# FreidoraAireCuki.net
KiCad netlist of a schematic drawn in Altium Designer
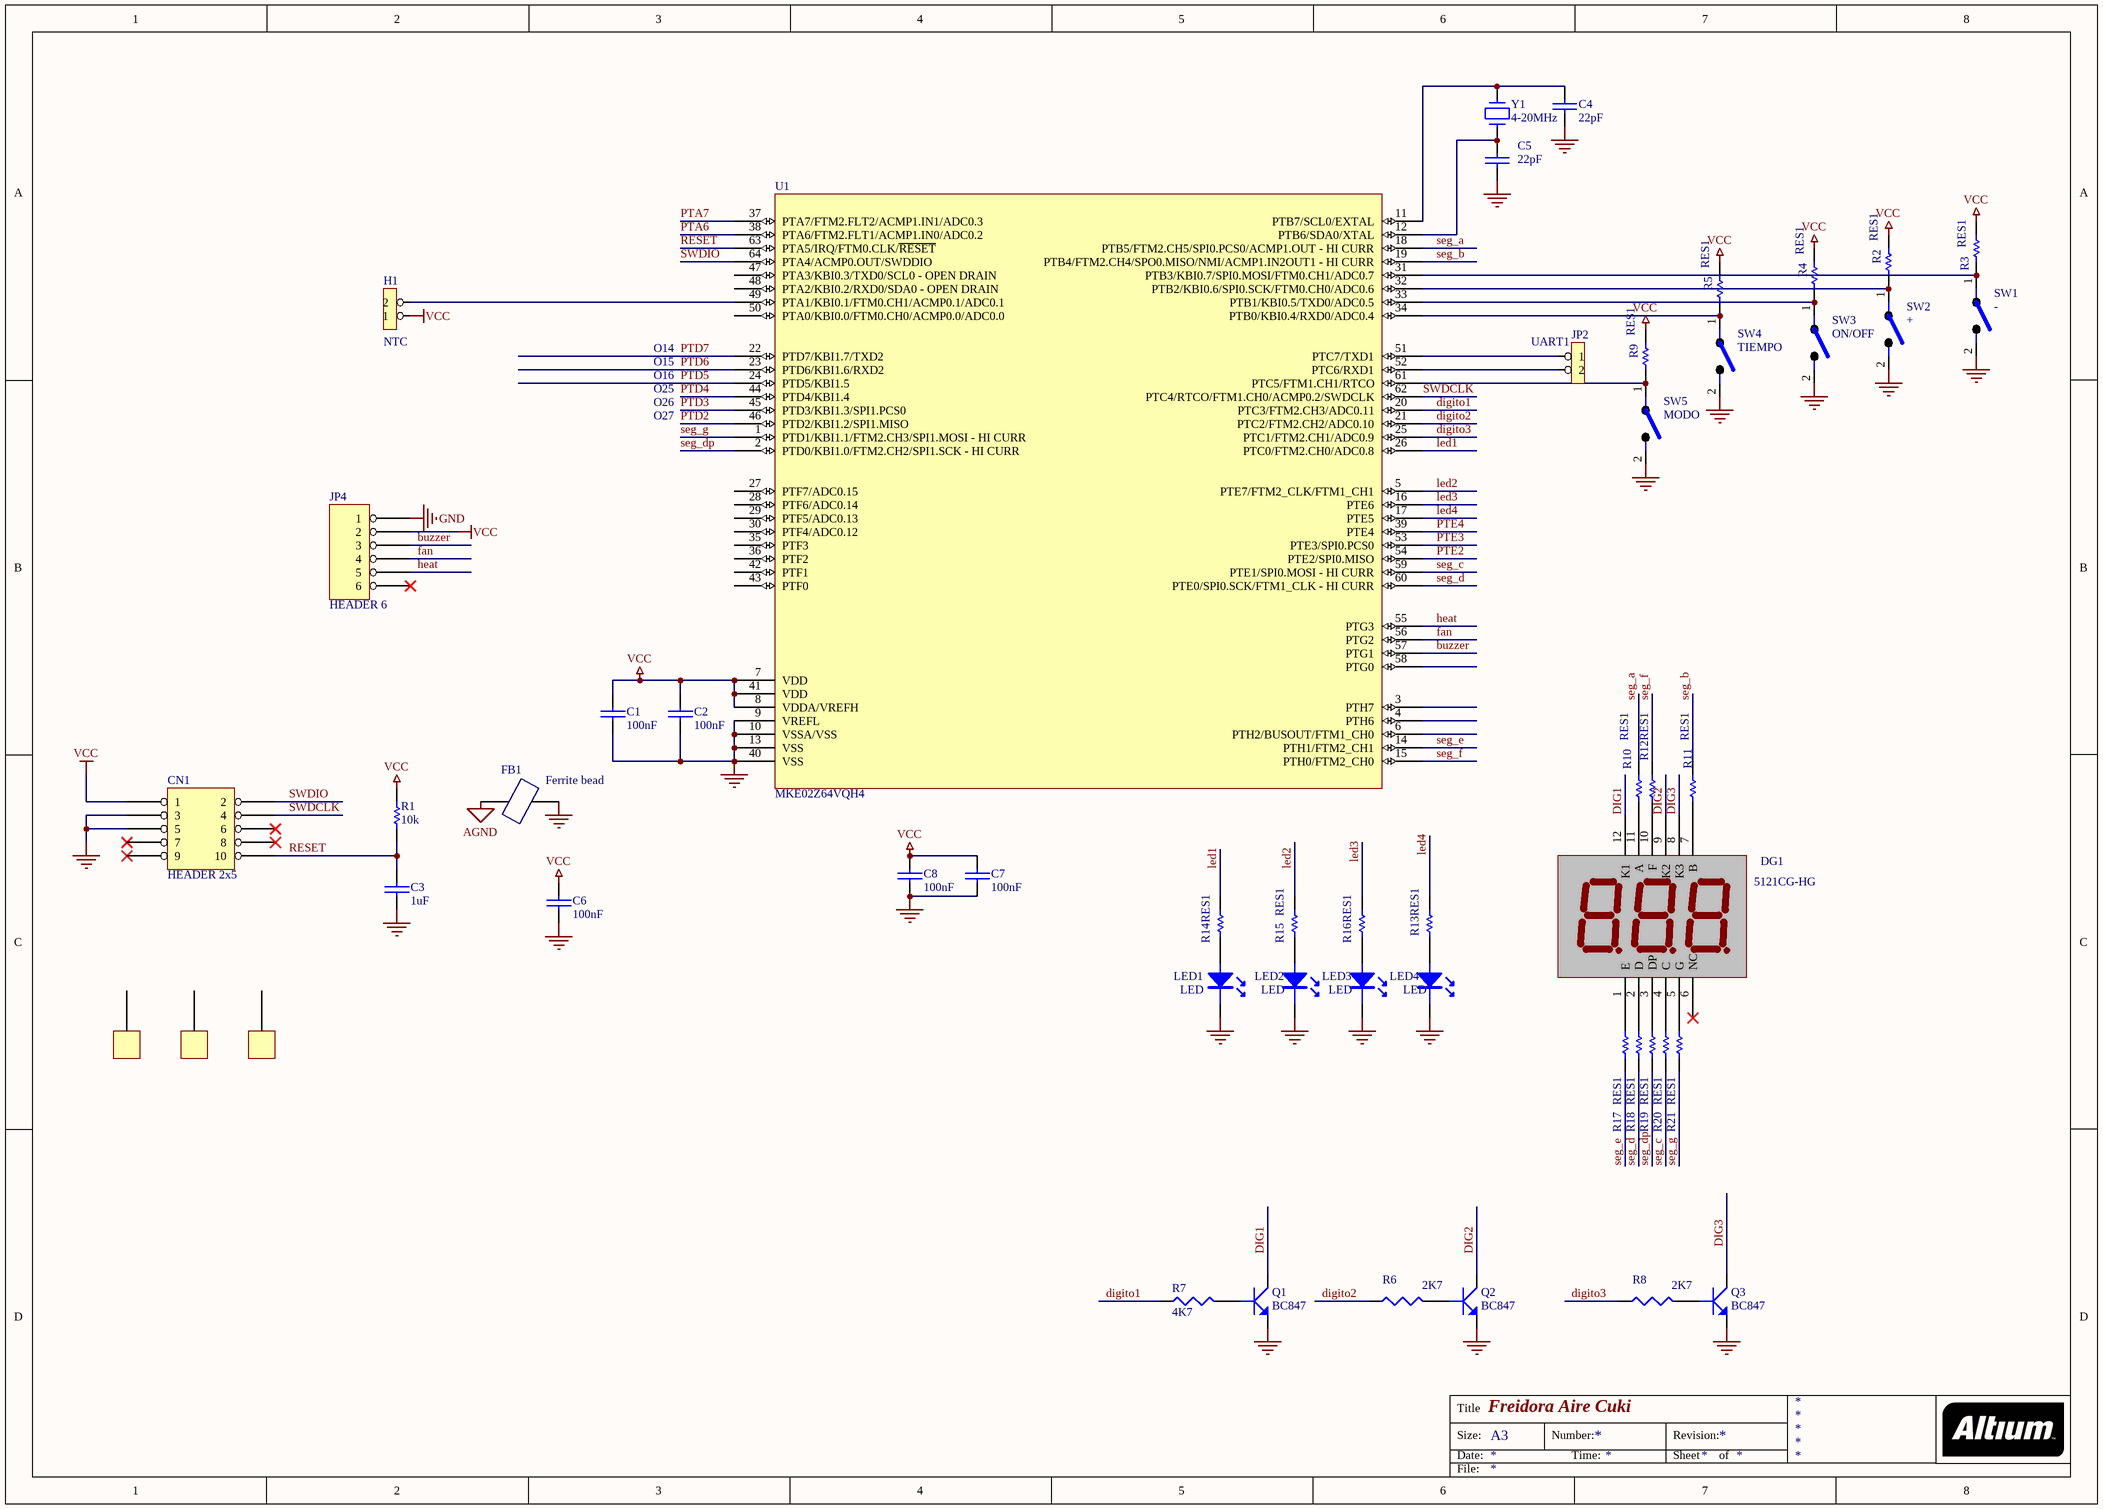
[diagram p0: FreidoraAireCuki.SchDoc]

(export (version "E")
  (design (tool "Eeschema 10.0.6"))
  (components
    (comp (ref "C1")
      (value "100nF")
      (footprint "C-0805_N")
      (description "Non polarized capacitor")
      (libsource (lib "DEKSOR") (part "CAP"))
    )
    (comp (ref "C2")
      (value "100nF")
      (footprint "C-0805_N")
      (description "Non polarized capacitor")
      (libsource (lib "DEKSOR") (part "CAP"))
    )
    (comp (ref "C3")
      (value "1uF")
      (footprint "C-0805_N")
      (description "Non polarized capacitor")
      (libsource (lib "DEKSOR") (part "CAP"))
    )
    (comp (ref "C4")
      (value "22pF")
      (footprint "C-0805_N")
      (description "Non polarized capacitor")
      (libsource (lib "DEKSOR SCH") (part "CAP"))
    )
    (comp (ref "C5")
      (value "22pF")
      (footprint "C-0805_N")
      (description "Non polarized capacitor")
      (libsource (lib "DEKSOR SCH") (part "CAP"))
    )
    (comp (ref "C6")
      (value "100nF")
      (footprint "C-0805_N")
      (description "Non polarized capacitor")
      (libsource (lib "DEKSOR") (part "CAP"))
    )
    (comp (ref "C7")
      (value "100nF")
      (footprint "C-0805_N")
      (description "Non polarized capacitor")
      (libsource (lib "DEKSOR SCH") (part "CAP"))
    )
    (comp (ref "C8")
      (value "100nF")
      (footprint "C-0805_N")
      (description "Non polarized capacitor")
      (libsource (lib "DEKSOR") (part "CAP"))
    )
    (comp (ref "CN1")
      (value "HEADER 2x5")
      (footprint "SIP2X5")
      (libsource (lib "DEKSOR") (part "HEADER 5X2"))
    )
    (comp (ref "DG1")
      (value "5121CG-HG")
      (footprint "DIGIT_3_400")
      (description "Dígito 0.52' cátodo común verde")
      (libsource (lib "DEKSOR") (part "DIGITO x 3 400"))
    )
    (comp (ref "FB1")
      (value "Ferrite bead")
      (footprint "C-0805_N")
      (libsource (lib "DEKSOR SCH") (part "Ferrite bead"))
    )
    (comp (ref "H1") (value "NTC") (footprint "SIP2") (libsource (lib "") (part "HEADER 2_1")))
    (comp (ref "JP2") (value "UART1") (footprint "SIP2") (libsource (lib "DEKSOR SCH") (part "HEADER 2")))
    (comp (ref "JP4") (value "HEADER 6") (footprint "SIP6") (libsource (lib "DEKSOR SCH") (part "HEADER 6")))
    (comp (ref "LED1") (value "LED") (footprint "LED3MM") (libsource (lib "DEKSOR SCH") (part "LED")))
    (comp (ref "LED2") (value "LED") (footprint "LED3MM") (libsource (lib "DEKSOR SCH") (part "LED")))
    (comp (ref "LED3") (value "LED") (footprint "LED3MM") (libsource (lib "DEKSOR SCH") (part "LED")))
    (comp (ref "LED4") (value "LED") (footprint "LED3MM") (libsource (lib "DEKSOR SCH") (part "LED")))
    (comp (ref "Q1")
      (value "BC847")
      (footprint "SOT23_BOTTOM")
      (description "NPN transistor bipolar")
      (libsource (lib "DEKSOR SCH") (part "BC847"))
    )
    (comp (ref "Q2")
      (value "BC847")
      (footprint "SOT23_BOTTOM")
      (description "NPN transistor bipolar")
      (libsource (lib "DEKSOR SCH") (part "BC847"))
    )
    (comp (ref "Q3")
      (value "BC847")
      (footprint "SOT23_BOTTOM")
      (description "NPN transistor bipolar")
      (libsource (lib "DEKSOR SCH") (part "BC847"))
    )
    (comp (ref "R1")
      (value "10k")
      (footprint "R-0805_N_WAVE")
      (description "Resistor SMD 0805")
      (fields (field (name "PUBLISHER") "Altium Limited"))
      (libsource (lib "DEKSOR") (part "Res SMD 0805"))
    )
    (comp (ref "R2")
      (value "RES1")
      (footprint "0805BOTTOM")
      (description "Resistor")
      (fields (field (name "PUBLISHER") "Altium Limited"))
      (libsource (lib "DEKSOR SCH") (part "RES1"))
    )
    (comp (ref "R3")
      (value "RES1")
      (footprint "0805BOTTOM")
      (description "Resistor")
      (fields (field (name "PUBLISHER") "Altium Limited"))
      (libsource (lib "DEKSOR SCH") (part "RES1"))
    )
    (comp (ref "R4")
      (value "RES1")
      (footprint "0805BOTTOM")
      (description "Resistor")
      (fields (field (name "PUBLISHER") "Altium Limited"))
      (libsource (lib "DEKSOR SCH") (part "RES1"))
    )
    (comp (ref "R5")
      (value "RES1")
      (footprint "0805BOTTOM")
      (description "Resistor")
      (fields (field (name "PUBLISHER") "Altium Limited"))
      (libsource (lib "DEKSOR SCH") (part "RES1"))
    )
    (comp (ref "R6")
      (value "2K7")
      (footprint "R-0805_N_WAVE")
      (description "Resistor")
      (libsource (lib "*") (part "RES"))
    )
    (comp (ref "R7")
      (value "4K7")
      (footprint "R-0805_N_WAVE")
      (description "Resistor")
      (libsource (lib "*") (part "RES"))
    )
    (comp (ref "R8")
      (value "2K7")
      (footprint "R-0805_N_WAVE")
      (description "Resistor")
      (libsource (lib "*") (part "RES"))
    )
    (comp (ref "R9")
      (value "RES1")
      (footprint "0805BOTTOM")
      (description "Resistor")
      (fields (field (name "PUBLISHER") "Altium Limited"))
      (libsource (lib "DEKSOR SCH") (part "RES1"))
    )
    (comp (ref "R10")
      (value "RES1")
      (footprint "0805BOTTOM")
      (description "Resistor")
      (fields (field (name "PUBLISHER") "Altium Limited"))
      (libsource (lib "DEKSOR SCH") (part "RES1"))
    )
    (comp (ref "R11")
      (value "RES1")
      (footprint "0805BOTTOM")
      (description "Resistor")
      (fields (field (name "PUBLISHER") "Altium Limited"))
      (libsource (lib "DEKSOR SCH") (part "RES1"))
    )
    (comp (ref "R12")
      (value "RES1")
      (footprint "0805BOTTOM")
      (description "Resistor")
      (fields (field (name "PUBLISHER") "Altium Limited"))
      (libsource (lib "DEKSOR SCH") (part "RES1"))
    )
    (comp (ref "R13")
      (value "RES1")
      (footprint "0805BOTTOM")
      (description "Resistor")
      (fields (field (name "PUBLISHER") "Altium Limited"))
      (libsource (lib "DEKSOR SCH") (part "RES1"))
    )
    (comp (ref "R14")
      (value "RES1")
      (footprint "0805BOTTOM")
      (description "Resistor")
      (fields (field (name "PUBLISHER") "Altium Limited"))
      (libsource (lib "DEKSOR SCH") (part "RES1"))
    )
    (comp (ref "R15")
      (value "RES1")
      (footprint "0805BOTTOM")
      (description "Resistor")
      (fields (field (name "PUBLISHER") "Altium Limited"))
      (libsource (lib "DEKSOR SCH") (part "RES1"))
    )
    (comp (ref "R16")
      (value "RES1")
      (footprint "0805BOTTOM")
      (description "Resistor")
      (fields (field (name "PUBLISHER") "Altium Limited"))
      (libsource (lib "DEKSOR SCH") (part "RES1"))
    )
    (comp (ref "R17")
      (value "RES1")
      (footprint "0805BOTTOM")
      (description "Resistor")
      (fields (field (name "PUBLISHER") "Altium Limited"))
      (libsource (lib "DEKSOR SCH") (part "RES1"))
    )
    (comp (ref "R18")
      (value "RES1")
      (footprint "0805BOTTOM")
      (description "Resistor")
      (fields (field (name "PUBLISHER") "Altium Limited"))
      (libsource (lib "DEKSOR SCH") (part "RES1"))
    )
    (comp (ref "R19")
      (value "RES1")
      (footprint "0805BOTTOM")
      (description "Resistor")
      (fields (field (name "PUBLISHER") "Altium Limited"))
      (libsource (lib "DEKSOR SCH") (part "RES1"))
    )
    (comp (ref "R20")
      (value "RES1")
      (footprint "0805BOTTOM")
      (description "Resistor")
      (fields (field (name "PUBLISHER") "Altium Limited"))
      (libsource (lib "DEKSOR SCH") (part "RES1"))
    )
    (comp (ref "R21")
      (value "RES1")
      (footprint "0805BOTTOM")
      (description "Resistor")
      (fields (field (name "PUBLISHER") "Altium Limited"))
      (libsource (lib "DEKSOR SCH") (part "RES1"))
    )
    (comp (ref "SW1") (value "-") (footprint "ZIPPY-TS") (libsource (lib "DEKSOR SCH") (part "TECLA")))
    (comp (ref "SW2") (value "+") (footprint "ZIPPY-TS") (libsource (lib "DEKSOR SCH") (part "TECLA")))
    (comp (ref "SW3") (value "ON/OFF") (footprint "ZIPPY-TS") (libsource (lib "DEKSOR SCH") (part "TECLA")))
    (comp (ref "SW4") (value "TIEMPO") (footprint "ZIPPY-TS") (libsource (lib "DEKSOR SCH") (part "TECLA")))
    (comp (ref "SW5") (value "MODO") (footprint "ZIPPY-TS") (libsource (lib "DEKSOR SCH") (part "TECLA")))
    (comp (ref "TORR1") (value "~") (footprint "TORRETA") (libsource (lib "DEKSOR SCH") (part "TORRETA")))
    (comp (ref "TORR2") (value "~") (footprint "TORRETA") (libsource (lib "DEKSOR SCH") (part "TORRETA")))
    (comp (ref "TORR3") (value "~") (footprint "TORRETA") (libsource (lib "DEKSOR SCH") (part "TORRETA")))
    (comp (ref "U1")
      (value "MKE02Z64VQH4")
      (footprint "QFP64")
      (description "IC MCU 32BIT 64KB FLASH 64QFP")
      (fields (field (name "MANUFACTURER") "Freescale Semiconductor"))
      (libsource (lib "DEKSOR") (part "MKE02Z64VQH4"))
    )
    (comp (ref "Y1")
      (value "4-20MHz")
      (footprint "XTAL1")
      (description "CRYSTAL")
      (libsource (lib "DEKSOR SCH") (part "CRYSTAL"))
    )
  )
  (nets
    (net (code "1") (name "/DIG1") (class "Default")
      (node (ref "DG1") (pin "12") (pinfunction "K1_12") (pintype "passive"))
      (node (ref "Q1") (pin "3") (pinfunction "C_3") (pintype "passive"))
    )
    (net (code "2") (name "/DIG2") (class "Default")
      (node (ref "DG1") (pin "9") (pinfunction "K2_9") (pintype "passive"))
      (node (ref "Q2") (pin "3") (pinfunction "C_3") (pintype "passive"))
    )
    (net (code "3") (name "/DIG3") (class "Default")
      (node (ref "DG1") (pin "8") (pinfunction "K3_8") (pintype "passive"))
      (node (ref "Q3") (pin "3") (pinfunction "C_3") (pintype "passive"))
    )
    (net (code "4") (name "/PTA6") (class "Default")
      (node (ref "U1") (pin "38") (pinfunction "PTA6/FTM2.FLT1/ACMP1.IN0/ADC0.2_38") (pintype "bidirectional"))
    )
    (net (code "5") (name "/PTA7") (class "Default")
      (node (ref "U1") (pin "37") (pinfunction "PTA7/FTM2.FLT2/ACMP1.IN1/ADC0.3_37") (pintype "bidirectional"))
    )
    (net (code "6") (name "/PTD2") (class "Default")
      (node (ref "U1") (pin "46") (pinfunction "PTD2/KBI1.2/SPI1.MISO_46") (pintype "bidirectional"))
    )
    (net (code "7") (name "/PTD3") (class "Default")
      (node (ref "U1") (pin "45") (pinfunction "PTD3/KBI1.3/SPI1.PCS0_45") (pintype "bidirectional"))
    )
    (net (code "8") (name "/PTD4") (class "Default")
      (node (ref "U1") (pin "44") (pinfunction "PTD4/KBI1.4_44") (pintype "bidirectional"))
    )
    (net (code "9") (name "/PTD5") (class "Default")
      (node (ref "U1") (pin "24") (pinfunction "PTD5/KBI1.5_24") (pintype "bidirectional"))
    )
    (net (code "10") (name "/PTD6") (class "Default")
      (node (ref "U1") (pin "23") (pinfunction "PTD6/KBI1.6/RXD2_23") (pintype "bidirectional"))
    )
    (net (code "11") (name "/PTD7") (class "Default")
      (node (ref "U1") (pin "22") (pinfunction "PTD7/KBI1.7/TXD2_22") (pintype "bidirectional"))
    )
    (net (code "12") (name "/PTE2") (class "Default")
      (node (ref "U1") (pin "54") (pinfunction "PTE2/SPI0.MISO_54") (pintype "bidirectional"))
    )
    (net (code "13") (name "/PTE3") (class "Default")
      (node (ref "U1") (pin "53") (pinfunction "PTE3/SPI0.PCS0_53") (pintype "bidirectional"))
    )
    (net (code "14") (name "/PTE4") (class "Default")
      (node (ref "U1") (pin "39") (pinfunction "PTE4_39") (pintype "bidirectional"))
    )
    (net (code "15") (name "/RESET") (class "Default")
      (node (ref "C3") (pin "1") (pintype "passive"))
      (node (ref "CN1") (pin "10") (pinfunction "10_10") (pintype "passive"))
      (node (ref "R1") (pin "1") (pinfunction "1_1") (pintype "passive"))
      (node (ref "U1") (pin "63") (pinfunction "PTA5/IRQ/FTM0.CLK/~{RESET}_63") (pintype "bidirectional"))
    )
    (net (code "16") (name "/SWDCLK") (class "Default")
      (node (ref "CN1") (pin "4") (pinfunction "4_4") (pintype "passive"))
      (node (ref "U1") (pin "62") (pinfunction "PTC4/RTCO/FTM1.CH0/ACMP0.2/SWDCLK_62") (pintype "bidirectional"))
    )
    (net (code "17") (name "/SWDIO") (class "Default")
      (node (ref "CN1") (pin "2") (pinfunction "2_2") (pintype "passive"))
      (node (ref "U1") (pin "64") (pinfunction "PTA4/ACMP0.OUT/SWDDIO_64") (pintype "bidirectional"))
    )
    (net (code "18") (name "/buzzer") (class "Default")
      (node (ref "JP4") (pin "3") (pinfunction "3_3") (pintype "passive"))
      (node (ref "U1") (pin "57") (pinfunction "PTG1_57") (pintype "bidirectional"))
    )
    (net (code "19") (name "/digito1") (class "Default")
      (node (ref "R7") (pin "1") (pinfunction "1_1") (pintype "passive"))
      (node (ref "U1") (pin "20") (pinfunction "PTC3/FTM2.CH3/ADC0.11_20") (pintype "bidirectional"))
    )
    (net (code "20") (name "/digito2") (class "Default")
      (node (ref "R6") (pin "1") (pinfunction "1_1") (pintype "passive"))
      (node (ref "U1") (pin "21") (pinfunction "PTC2/FTM2.CH2/ADC0.10_21") (pintype "bidirectional"))
    )
    (net (code "21") (name "/digito3") (class "Default")
      (node (ref "R8") (pin "1") (pinfunction "1_1") (pintype "passive"))
      (node (ref "U1") (pin "25") (pinfunction "PTC1/FTM2.CH1/ADC0.9_25") (pintype "bidirectional"))
    )
    (net (code "22") (name "/fan") (class "Default")
      (node (ref "JP4") (pin "4") (pinfunction "4_4") (pintype "passive"))
      (node (ref "U1") (pin "56") (pinfunction "PTG2_56") (pintype "bidirectional"))
    )
    (net (code "23") (name "/heat") (class "Default")
      (node (ref "JP4") (pin "5") (pinfunction "5_5") (pintype "passive"))
      (node (ref "U1") (pin "55") (pinfunction "PTG3_55") (pintype "bidirectional"))
    )
    (net (code "24") (name "/led1") (class "Default")
      (node (ref "R14") (pin "2") (pinfunction "2_2") (pintype "passive"))
      (node (ref "U1") (pin "26") (pinfunction "PTC0/FTM2.CH0/ADC0.8_26") (pintype "bidirectional"))
    )
    (net (code "25") (name "/led2") (class "Default")
      (node (ref "R15") (pin "2") (pinfunction "2_2") (pintype "passive"))
      (node (ref "U1") (pin "5") (pinfunction "PTE7/FTM2_CLK/FTM1_CH1_5") (pintype "bidirectional"))
    )
    (net (code "26") (name "/led3") (class "Default")
      (node (ref "R16") (pin "2") (pinfunction "2_2") (pintype "passive"))
      (node (ref "U1") (pin "16") (pinfunction "PTE6_16") (pintype "bidirectional"))
    )
    (net (code "27") (name "/led4") (class "Default")
      (node (ref "R13") (pin "2") (pinfunction "2_2") (pintype "passive"))
      (node (ref "U1") (pin "17") (pinfunction "PTE5_17") (pintype "bidirectional"))
    )
    (net (code "28") (name "/seg_a") (class "Default")
      (node (ref "R10") (pin "2") (pinfunction "2_2") (pintype "passive"))
      (node (ref "U1") (pin "18") (pinfunction "PTB5/FTM2.CH5/SPI0.PCS0/ACMP1.OUT_-_HI_CURR_18") (pintype "bidirectional"))
    )
    (net (code "29") (name "/seg_b") (class "Default")
      (node (ref "R11") (pin "2") (pinfunction "2_2") (pintype "passive"))
      (node (ref "U1") (pin "19") (pinfunction "PTB4/FTM2.CH4/SPO0.MISO/NMI/ACMP1.IN2OUT1_-_HI_CURR_19") (pintype "bidirectional"))
    )
    (net (code "30") (name "/seg_c") (class "Default")
      (node (ref "R20") (pin "1") (pinfunction "1_1") (pintype "passive"))
      (node (ref "U1") (pin "59") (pinfunction "PTE1/SPI0.MOSI_-_HI_CURR_59") (pintype "bidirectional"))
    )
    (net (code "31") (name "/seg_d") (class "Default")
      (node (ref "R18") (pin "1") (pinfunction "1_1") (pintype "passive"))
      (node (ref "U1") (pin "60") (pinfunction "PTE0/SPI0.SCK/FTM1_CLK_-_HI_CURR_60") (pintype "bidirectional"))
    )
    (net (code "32") (name "/seg_dp") (class "Default")
      (node (ref "R19") (pin "1") (pinfunction "1_1") (pintype "passive"))
      (node (ref "U1") (pin "2") (pinfunction "PTD0/KBI1.0/FTM2.CH2/SPI1.SCK_-_HI_CURR_2") (pintype "bidirectional"))
    )
    (net (code "33") (name "/seg_e") (class "Default")
      (node (ref "R17") (pin "1") (pinfunction "1_1") (pintype "passive"))
      (node (ref "U1") (pin "14") (pinfunction "PTH1/FTM2_CH1_14") (pintype "bidirectional"))
    )
    (net (code "34") (name "/seg_f") (class "Default")
      (node (ref "R12") (pin "2") (pinfunction "2_2") (pintype "passive"))
      (node (ref "U1") (pin "15") (pinfunction "PTH0/FTM2_CH0_15") (pintype "bidirectional"))
    )
    (net (code "35") (name "/seg_g") (class "Default")
      (node (ref "R21") (pin "1") (pinfunction "1_1") (pintype "passive"))
      (node (ref "U1") (pin "1") (pinfunction "PTD1/KBI1.1/FTM2.CH3/SPI1.MOSI_-_HI_CURR_1") (pintype "bidirectional"))
    )
    (net (code "36") (name "AGND") (class "Default") (node (ref "FB1") (pin "2") (pintype "passive")))
    (net (code "37") (name "GND") (class "Default")
      (node (ref "C1") (pin "2") (pintype "passive"))
      (node (ref "C2") (pin "2") (pintype "passive"))
      (node (ref "C3") (pin "2") (pintype "passive"))
      (node (ref "C4") (pin "1") (pintype "passive"))
      (node (ref "C5") (pin "1") (pintype "passive"))
      (node (ref "C6") (pin "2") (pintype "passive"))
      (node (ref "C7") (pin "2") (pintype "passive"))
      (node (ref "C8") (pin "2") (pintype "passive"))
      (node (ref "CN1") (pin "3") (pinfunction "3_3") (pintype "passive"))
      (node (ref "CN1") (pin "5") (pinfunction "5_5") (pintype "passive"))
      (node (ref "FB1") (pin "1") (pintype "passive"))
      (node (ref "JP4") (pin "1") (pinfunction "1_1") (pintype "passive"))
      (node (ref "LED1") (pin "2") (pinfunction "K_2") (pintype "passive"))
      (node (ref "LED2") (pin "2") (pinfunction "K_2") (pintype "passive"))
      (node (ref "LED3") (pin "2") (pinfunction "K_2") (pintype "passive"))
      (node (ref "LED4") (pin "2") (pinfunction "K_2") (pintype "passive"))
      (node (ref "Q1") (pin "2") (pinfunction "E_2") (pintype "passive"))
      (node (ref "Q2") (pin "2") (pinfunction "E_2") (pintype "passive"))
      (node (ref "Q3") (pin "2") (pinfunction "E_2") (pintype "passive"))
      (node (ref "SW1") (pin "2") (pintype "passive"))
      (node (ref "SW2") (pin "2") (pintype "passive"))
      (node (ref "SW3") (pin "2") (pintype "passive"))
      (node (ref "SW4") (pin "2") (pintype "passive"))
      (node (ref "SW5") (pin "2") (pintype "passive"))
      (node (ref "U1") (pin "10") (pinfunction "VSSA/VSS_10") (pintype "power_in"))
      (node (ref "U1") (pin "13") (pinfunction "VSS_13") (pintype "power_in"))
      (node (ref "U1") (pin "40") (pinfunction "VSS_40") (pintype "power_in"))
      (node (ref "U1") (pin "9") (pinfunction "VREFL_9") (pintype "power_in"))
    )
    (net (code "38") (name "Net-(DG1-A)") (class "Default")
      (node (ref "DG1") (pin "11") (pinfunction "A_11") (pintype "passive"))
      (node (ref "R10") (pin "1") (pinfunction "1_1") (pintype "passive"))
    )
    (net (code "39") (name "Net-(DG1-B)") (class "Default")
      (node (ref "DG1") (pin "7") (pinfunction "B_7") (pintype "passive"))
      (node (ref "R11") (pin "1") (pinfunction "1_1") (pintype "passive"))
    )
    (net (code "40") (name "Net-(DG1-C)") (class "Default")
      (node (ref "DG1") (pin "4") (pinfunction "C_4") (pintype "passive"))
      (node (ref "R20") (pin "2") (pinfunction "2_2") (pintype "passive"))
    )
    (net (code "41") (name "Net-(DG1-D)") (class "Default")
      (node (ref "DG1") (pin "2") (pinfunction "D_2") (pintype "passive"))
      (node (ref "R18") (pin "2") (pinfunction "2_2") (pintype "passive"))
    )
    (net (code "42") (name "Net-(DG1-DP)") (class "Default")
      (node (ref "DG1") (pin "3") (pinfunction "DP_3") (pintype "passive"))
      (node (ref "R19") (pin "2") (pinfunction "2_2") (pintype "passive"))
    )
    (net (code "43") (name "Net-(DG1-E)") (class "Default")
      (node (ref "DG1") (pin "1") (pinfunction "E_1") (pintype "passive"))
      (node (ref "R17") (pin "2") (pinfunction "2_2") (pintype "passive"))
    )
    (net (code "44") (name "Net-(DG1-F)") (class "Default")
      (node (ref "DG1") (pin "10") (pinfunction "F_10") (pintype "passive"))
      (node (ref "R12") (pin "1") (pinfunction "1_1") (pintype "passive"))
    )
    (net (code "45") (name "Net-(DG1-G)") (class "Default")
      (node (ref "DG1") (pin "5") (pinfunction "G_5") (pintype "passive"))
      (node (ref "R21") (pin "2") (pinfunction "2_2") (pintype "passive"))
    )
    (net (code "46") (name "Net-(LED1-A)") (class "Default")
      (node (ref "LED1") (pin "1") (pinfunction "A_1") (pintype "passive"))
      (node (ref "R14") (pin "1") (pinfunction "1_1") (pintype "passive"))
    )
    (net (code "47") (name "Net-(LED2-A)") (class "Default")
      (node (ref "LED2") (pin "1") (pinfunction "A_1") (pintype "passive"))
      (node (ref "R15") (pin "1") (pinfunction "1_1") (pintype "passive"))
    )
    (net (code "48") (name "Net-(LED3-A)") (class "Default")
      (node (ref "LED3") (pin "1") (pinfunction "A_1") (pintype "passive"))
      (node (ref "R16") (pin "1") (pinfunction "1_1") (pintype "passive"))
    )
    (net (code "49") (name "Net-(LED4-A)") (class "Default")
      (node (ref "LED4") (pin "1") (pinfunction "A_1") (pintype "passive"))
      (node (ref "R13") (pin "1") (pinfunction "1_1") (pintype "passive"))
    )
    (net (code "50") (name "Net-(Q1-B)") (class "Default")
      (node (ref "Q1") (pin "1") (pinfunction "B_1") (pintype "passive"))
      (node (ref "R7") (pin "2") (pinfunction "2_2") (pintype "passive"))
    )
    (net (code "51") (name "Net-(Q2-B)") (class "Default")
      (node (ref "Q2") (pin "1") (pinfunction "B_1") (pintype "passive"))
      (node (ref "R6") (pin "2") (pinfunction "2_2") (pintype "passive"))
    )
    (net (code "52") (name "Net-(Q3-B)") (class "Default")
      (node (ref "Q3") (pin "1") (pinfunction "B_1") (pintype "passive"))
      (node (ref "R8") (pin "2") (pinfunction "2_2") (pintype "passive"))
    )
    (net (code "53") (name "Net-(U1-PTA1{slash}KBI0.1{slash}FTM0.CH1{slash}ACMP0.1{slash}ADC0.1)") (class "Default")
      (node (ref "H1") (pin "2") (pinfunction "2_2") (pintype "passive"))
      (node (ref "U1") (pin "49") (pinfunction "PTA1/KBI0.1/FTM0.CH1/ACMP0.1/ADC0.1_49") (pintype "bidirectional"))
    )
    (net (code "54") (name "Net-(U1-PTB0{slash}KBI0.4{slash}RXD0{slash}ADC0.4)") (class "Default")
      (node (ref "R5") (pin "1") (pinfunction "1_1") (pintype "passive"))
      (node (ref "SW4") (pin "1") (pintype "passive"))
      (node (ref "U1") (pin "34") (pinfunction "PTB0/KBI0.4/RXD0/ADC0.4_34") (pintype "bidirectional"))
    )
    (net (code "55") (name "Net-(U1-PTB1{slash}KBI0.5{slash}TXD0{slash}ADC0.5)") (class "Default")
      (node (ref "R4") (pin "1") (pinfunction "1_1") (pintype "passive"))
      (node (ref "SW3") (pin "1") (pintype "passive"))
      (node (ref "U1") (pin "33") (pinfunction "PTB1/KBI0.5/TXD0/ADC0.5_33") (pintype "bidirectional"))
    )
    (net (code "56") (name "Net-(U1-PTB2{slash}KBI0.6{slash}SPI0.SCK{slash}FTM0.CH0{slash}ADC0.6)") (class "Default")
      (node (ref "R2") (pin "1") (pinfunction "1_1") (pintype "passive"))
      (node (ref "SW2") (pin "1") (pintype "passive"))
      (node (ref "U1") (pin "32") (pinfunction "PTB2/KBI0.6/SPI0.SCK/FTM0.CH0/ADC0.6_32") (pintype "bidirectional"))
    )
    (net (code "57") (name "Net-(U1-PTB3{slash}KBI0.7{slash}SPI0.MOSI{slash}FTM0.CH1{slash}ADC0.7)") (class "Default")
      (node (ref "R3") (pin "1") (pinfunction "1_1") (pintype "passive"))
      (node (ref "SW1") (pin "1") (pintype "passive"))
      (node (ref "U1") (pin "31") (pinfunction "PTB3/KBI0.7/SPI0.MOSI/FTM0.CH1/ADC0.7_31") (pintype "bidirectional"))
    )
    (net (code "58") (name "Net-(U1-PTB6{slash}SDA0{slash}XTAL)") (class "Default")
      (node (ref "C5") (pin "2") (pintype "passive"))
      (node (ref "U1") (pin "12") (pinfunction "PTB6/SDA0/XTAL_12") (pintype "bidirectional"))
      (node (ref "Y1") (pin "2") (pintype "passive"))
    )
    (net (code "59") (name "Net-(U1-PTB7{slash}SCL0{slash}EXTAL)") (class "Default")
      (node (ref "C4") (pin "2") (pintype "passive"))
      (node (ref "U1") (pin "11") (pinfunction "PTB7/SCL0/EXTAL_11") (pintype "bidirectional"))
      (node (ref "Y1") (pin "1") (pintype "passive"))
    )
    (net (code "60") (name "Net-(U1-PTC5{slash}FTM1.CH1{slash}RTCO)") (class "Default")
      (node (ref "R9") (pin "1") (pinfunction "1_1") (pintype "passive"))
      (node (ref "SW5") (pin "1") (pintype "passive"))
      (node (ref "U1") (pin "61") (pinfunction "PTC5/FTM1.CH1/RTCO_61") (pintype "bidirectional"))
    )
    (net (code "61") (name "Net-(U1-PTC6{slash}RXD1)") (class "Default")
      (node (ref "JP2") (pin "2") (pinfunction "2_2") (pintype "passive"))
      (node (ref "U1") (pin "52") (pinfunction "PTC6/RXD1_52") (pintype "bidirectional"))
    )
    (net (code "62") (name "Net-(U1-PTC7{slash}TXD1)") (class "Default")
      (node (ref "JP2") (pin "1") (pinfunction "1_1") (pintype "passive"))
      (node (ref "U1") (pin "51") (pinfunction "PTC7/TXD1_51") (pintype "bidirectional"))
    )
    (net (code "63") (name "VCC") (class "Default")
      (node (ref "C1") (pin "1") (pintype "passive"))
      (node (ref "C2") (pin "1") (pintype "passive"))
      (node (ref "C6") (pin "1") (pintype "passive"))
      (node (ref "C7") (pin "1") (pintype "passive"))
      (node (ref "C8") (pin "1") (pintype "passive"))
      (node (ref "CN1") (pin "1") (pinfunction "1_1") (pintype "passive"))
      (node (ref "H1") (pin "1") (pinfunction "1_1") (pintype "passive"))
      (node (ref "JP4") (pin "2") (pinfunction "2_2") (pintype "passive"))
      (node (ref "R1") (pin "2") (pinfunction "2_2") (pintype "passive"))
      (node (ref "R2") (pin "2") (pinfunction "2_2") (pintype "passive"))
      (node (ref "R3") (pin "2") (pinfunction "2_2") (pintype "passive"))
      (node (ref "R4") (pin "2") (pinfunction "2_2") (pintype "passive"))
      (node (ref "R5") (pin "2") (pinfunction "2_2") (pintype "passive"))
      (node (ref "R9") (pin "2") (pinfunction "2_2") (pintype "passive"))
      (node (ref "U1") (pin "41") (pinfunction "VDD_41") (pintype "power_in"))
      (node (ref "U1") (pin "7") (pinfunction "VDD_7") (pintype "power_in"))
      (node (ref "U1") (pin "8") (pinfunction "VDDA/VREFH_8") (pintype "power_in"))
    )
    (net (code "64") (name "unconnected-(CN1-Pad6)") (class "Default")
      (node (ref "CN1") (pin "6") (pinfunction "6_6") (pintype "passive+no_connect"))
    )
    (net (code "65") (name "unconnected-(CN1-Pad7)") (class "Default")
      (node (ref "CN1") (pin "7") (pinfunction "7_7") (pintype "passive+no_connect"))
    )
    (net (code "66") (name "unconnected-(CN1-Pad8)") (class "Default")
      (node (ref "CN1") (pin "8") (pinfunction "8_8") (pintype "passive+no_connect"))
    )
    (net (code "67") (name "unconnected-(CN1-Pad9)") (class "Default")
      (node (ref "CN1") (pin "9") (pinfunction "9_9") (pintype "passive+no_connect"))
    )
    (net (code "68") (name "unconnected-(DG1-NC-Pad6)") (class "Default")
      (node (ref "DG1") (pin "6") (pinfunction "NC_6") (pintype "passive+no_connect"))
    )
    (net (code "69") (name "unconnected-(JP4-Pad6)") (class "Default")
      (node (ref "JP4") (pin "6") (pinfunction "6_6") (pintype "passive+no_connect"))
    )
    (net (code "70") (name "unconnected-(TORR1-Pad0)") (class "Default")
      (node (ref "TORR1") (pin "0") (pinfunction "0_0") (pintype "passive"))
    )
    (net (code "71") (name "unconnected-(TORR2-Pad0)") (class "Default")
      (node (ref "TORR2") (pin "0") (pinfunction "0_0") (pintype "passive"))
    )
    (net (code "72") (name "unconnected-(TORR3-Pad0)") (class "Default")
      (node (ref "TORR3") (pin "0") (pinfunction "0_0") (pintype "passive"))
    )
    (net (code "73") (name "unconnected-(U1-PTA0{slash}KBI0.0{slash}FTM0.CH0{slash}ACMP0.0{slash}ADC0.0-Pad50)") (class "Default")
      (node (ref "U1") (pin "50") (pinfunction "PTA0/KBI0.0/FTM0.CH0/ACMP0.0/ADC0.0_50") (pintype "bidirectional"))
    )
    (net (code "74") (name "unconnected-(U1-PTA2{slash}KBI0.2{slash}RXD0{slash}SDA0_-_OPEN_DRAIN-Pad48)") (class "Default")
      (node (ref "U1") (pin "48") (pinfunction "PTA2/KBI0.2/RXD0/SDA0_-_OPEN_DRAIN_48") (pintype "bidirectional"))
    )
    (net (code "75") (name "unconnected-(U1-PTA3{slash}KBI0.3{slash}TXD0{slash}SCL0_-_OPEN_DRAIN-Pad47)") (class "Default")
      (node (ref "U1") (pin "47") (pinfunction "PTA3/KBI0.3/TXD0/SCL0_-_OPEN_DRAIN_47") (pintype "bidirectional"))
    )
    (net (code "76") (name "unconnected-(U1-PTF0-Pad43)") (class "Default")
      (node (ref "U1") (pin "43") (pinfunction "PTF0_43") (pintype "bidirectional"))
    )
    (net (code "77") (name "unconnected-(U1-PTF1-Pad42)") (class "Default")
      (node (ref "U1") (pin "42") (pinfunction "PTF1_42") (pintype "bidirectional"))
    )
    (net (code "78") (name "unconnected-(U1-PTF2-Pad36)") (class "Default")
      (node (ref "U1") (pin "36") (pinfunction "PTF2_36") (pintype "bidirectional"))
    )
    (net (code "79") (name "unconnected-(U1-PTF3-Pad35)") (class "Default")
      (node (ref "U1") (pin "35") (pinfunction "PTF3_35") (pintype "bidirectional"))
    )
    (net (code "80") (name "unconnected-(U1-PTF4{slash}ADC0.12-Pad30)") (class "Default")
      (node (ref "U1") (pin "30") (pinfunction "PTF4/ADC0.12_30") (pintype "bidirectional"))
    )
    (net (code "81") (name "unconnected-(U1-PTF5{slash}ADC0.13-Pad29)") (class "Default")
      (node (ref "U1") (pin "29") (pinfunction "PTF5/ADC0.13_29") (pintype "bidirectional"))
    )
    (net (code "82") (name "unconnected-(U1-PTF6{slash}ADC0.14-Pad28)") (class "Default")
      (node (ref "U1") (pin "28") (pinfunction "PTF6/ADC0.14_28") (pintype "bidirectional"))
    )
    (net (code "83") (name "unconnected-(U1-PTF7{slash}ADC0.15-Pad27)") (class "Default")
      (node (ref "U1") (pin "27") (pinfunction "PTF7/ADC0.15_27") (pintype "bidirectional"))
    )
    (net (code "84") (name "unconnected-(U1-PTG0-Pad58)") (class "Default")
      (node (ref "U1") (pin "58") (pinfunction "PTG0_58") (pintype "bidirectional"))
    )
    (net (code "85") (name "unconnected-(U1-PTH2{slash}BUSOUT{slash}FTM1_CH0-Pad6)") (class "Default")
      (node (ref "U1") (pin "6") (pinfunction "PTH2/BUSOUT/FTM1_CH0_6") (pintype "bidirectional"))
    )
    (net (code "86") (name "unconnected-(U1-PTH6-Pad4)") (class "Default")
      (node (ref "U1") (pin "4") (pinfunction "PTH6_4") (pintype "bidirectional"))
    )
    (net (code "87") (name "unconnected-(U1-PTH7-Pad3)") (class "Default")
      (node (ref "U1") (pin "3") (pinfunction "PTH7_3") (pintype "bidirectional"))
    )
  )
)
